# Communication.net
KiCad netlist of a schematic drawn in Altium Designer
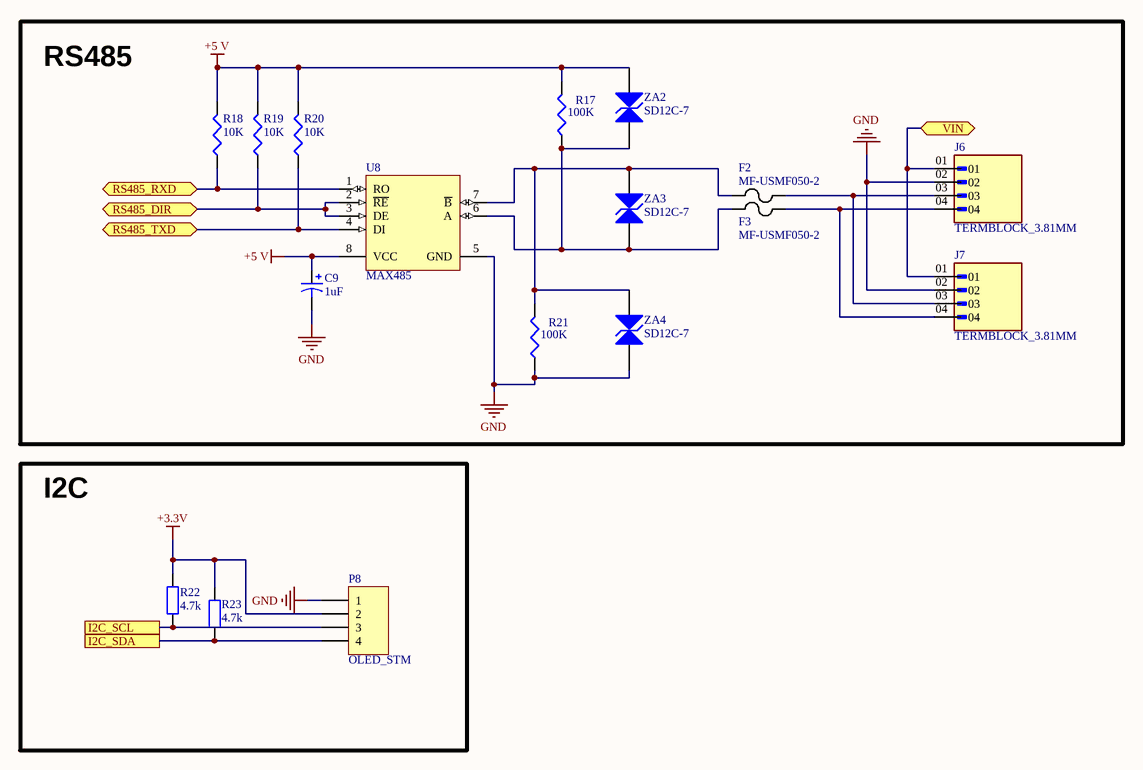
[diagram p0: Communication.SchDoc]

(export (version "E")
  (design (tool "Eeschema 10.0.6"))
  (components
    (comp (ref "C9")
      (value "1uF")
      (footprint "CAPC3225N")
      (description "Polarized Capacitor (Surface Mount)")
      (fields (field (name "PUBLISHER") "Altium Limited"))
      (libsource (lib "Miscellaneous Devices") (part "Cap Pol3"))
    )
    (comp (ref "F2")
      (value "MF-USMF050-2")
      (footprint "MF-USMF050-2")
      (description "PTC RESET FUSE 6V 3A 1812")
      (libsource (lib "Adox_Lib") (part "PTS18126V300"))
    )
    (comp (ref "F3")
      (value "MF-USMF050-2")
      (footprint "MF-USMF050-2")
      (description "PTC RESET FUSE 6V 3A 1812")
      (libsource (lib "Adox_Lib") (part "PTS18126V300"))
    )
    (comp (ref "J6")
      (value "TERMBLOCK_3.81MM")
      (footprint "TERMBLOCK_3.81MM_90DEG_4POS")
      (description "TERMBLOCK_3.81MM_90DEG_4POS (DigiKey: 1803293)")
      (libsource (lib "MH_Lib") (part "TERMBLOCK_3.81MM_90DEG_4POS"))
    )
    (comp (ref "J7")
      (value "TERMBLOCK_3.81MM")
      (footprint "TERMBLOCK_3.81MM_90DEG_4POS")
      (description "TERMBLOCK_3.81MM_90DEG_4POS (DigiKey: 1803293)")
      (libsource (lib "MH_Lib") (part "TERMBLOCK_3.81MM_90DEG_4POS"))
    )
    (comp (ref "P8")
      (value "OLED_STM")
      (footprint "CONNHDR_1X4_2.54MM")
      (description "Header, 4-Pin")
      (fields (field (name "PUBLISHER") "Altium Limited"))
      (libsource (lib "Miscellaneous Connectors") (part "MHDR1X4"))
    )
    (comp (ref "R17")
      (value "100K")
      (footprint "RESC2012N")
      (description "Resistor")
      (fields (field (name "PUBLISHER") "Altium Limited"))
      (libsource (lib "Miscellaneous Devices") (part "Res3"))
    )
    (comp (ref "R18")
      (value "10K")
      (footprint "RESC2012N")
      (description "Resistor")
      (fields (field (name "PUBLISHER") "Altium Limited"))
      (libsource (lib "Miscellaneous Devices") (part "Res3"))
    )
    (comp (ref "R19")
      (value "10K")
      (footprint "RESC2012N")
      (description "Resistor")
      (fields (field (name "PUBLISHER") "Altium Limited"))
      (libsource (lib "Miscellaneous Devices") (part "Res3"))
    )
    (comp (ref "R20")
      (value "10K")
      (footprint "RESC2012N")
      (description "Resistor")
      (fields (field (name "PUBLISHER") "Altium Limited"))
      (libsource (lib "Miscellaneous Devices") (part "Res3"))
    )
    (comp (ref "R21")
      (value "100K")
      (footprint "RESC2012N")
      (description "Resistor")
      (fields (field (name "PUBLISHER") "Altium Limited"))
      (libsource (lib "Miscellaneous Devices") (part "Res3"))
    )
    (comp (ref "R22")
      (value "4.7k")
      (footprint "RESC2012N")
      (description "Resistor")
      (fields (field (name "PUBLISHER") "Altium Limited"))
      (libsource (lib "Miscellaneous Devices") (part "Res2"))
    )
    (comp (ref "R23")
      (value "4.7k")
      (footprint "RESC2012N")
      (description "Resistor")
      (fields (field (name "PUBLISHER") "Altium Limited"))
      (libsource (lib "Miscellaneous Devices") (part "Res2"))
    )
    (comp (ref "U8")
      (value "MAX485")
      (footprint "MAX485")
      (description "Low-Power RS-485/RS-422 Multipoint Transceiver, 8-pin Narrow SOIC")
      (libsource (lib "MH_Lib") (part "MAX485"))
    )
    (comp (ref "ZA2")
      (value "SD12C-7")
      (footprint "SOD-323")
      (description "Transient voltage suppressor diode")
      (libsource (lib "Adox_Lib") (part "TVS Diode"))
    )
    (comp (ref "ZA3")
      (value "SD12C-7")
      (footprint "SOD-323")
      (description "Transient voltage suppressor diode")
      (libsource (lib "Adox_Lib") (part "TVS Diode"))
    )
    (comp (ref "ZA4")
      (value "SD12C-7")
      (footprint "SOD-323")
      (description "Transient voltage suppressor diode")
      (libsource (lib "Adox_Lib") (part "TVS Diode"))
    )
  )
  (nets
    (net (code "1") (name "+3.3V") (class "Default")
      (node (ref "P8") (pin "2") (pinfunction "2_2") (pintype "passive"))
      (node (ref "R22") (pin "2") (pinfunction "2_2") (pintype "passive"))
      (node (ref "R23") (pin "2") (pinfunction "2_2") (pintype "passive"))
    )
    (net (code "2") (name "+5 V") (class "Default")
      (node (ref "C9") (pin "1") (pinfunction "1_1") (pintype "passive"))
      (node (ref "R17") (pin "2") (pinfunction "2_2") (pintype "passive"))
      (node (ref "R18") (pin "2") (pinfunction "2_2") (pintype "passive"))
      (node (ref "R19") (pin "2") (pinfunction "2_2") (pintype "passive"))
      (node (ref "R20") (pin "2") (pinfunction "2_2") (pintype "passive"))
      (node (ref "U8") (pin "8") (pinfunction "VCC_8") (pintype "power_in"))
      (node (ref "ZA2") (pin "1") (pinfunction "1_1") (pintype "passive"))
    )
    (net (code "3") (name "/I2C_SCL") (class "Default")
      (node (ref "P8") (pin "3") (pinfunction "3_3") (pintype "passive"))
      (node (ref "R22") (pin "1") (pinfunction "1_1") (pintype "passive"))
    )
    (net (code "4") (name "/I2C_SDA") (class "Default")
      (node (ref "P8") (pin "4") (pinfunction "4_4") (pintype "passive"))
      (node (ref "R23") (pin "1") (pinfunction "1_1") (pintype "passive"))
    )
    (net (code "5") (name "/RS485_DIR") (class "Default")
      (node (ref "R19") (pin "1") (pinfunction "1_1") (pintype "passive"))
      (node (ref "U8") (pin "2") (pinfunction "~{RE}_2") (pintype "input"))
      (node (ref "U8") (pin "3") (pinfunction "DE_3") (pintype "input"))
    )
    (net (code "6") (name "/RS485_RXD") (class "Default")
      (node (ref "R18") (pin "1") (pinfunction "1_1") (pintype "passive"))
      (node (ref "U8") (pin "1") (pinfunction "RO_1") (pintype "bidirectional"))
    )
    (net (code "7") (name "/RS485_TXD") (class "Default")
      (node (ref "R20") (pin "1") (pinfunction "1_1") (pintype "passive"))
      (node (ref "U8") (pin "4") (pinfunction "DI_4") (pintype "input"))
    )
    (net (code "8") (name "/VIN") (class "Default")
      (node (ref "J6") (pin "01") (pinfunction "01_01") (pintype "passive"))
      (node (ref "J7") (pin "01") (pinfunction "01_01") (pintype "passive"))
    )
    (net (code "9") (name "GND") (class "Default")
      (node (ref "C9") (pin "2") (pinfunction "2_2") (pintype "passive"))
      (node (ref "J6") (pin "02") (pinfunction "02_02") (pintype "passive"))
      (node (ref "J7") (pin "02") (pinfunction "02_02") (pintype "passive"))
      (node (ref "P8") (pin "1") (pinfunction "1_1") (pintype "passive"))
      (node (ref "R21") (pin "1") (pinfunction "1_1") (pintype "passive"))
      (node (ref "U8") (pin "5") (pinfunction "GND_5") (pintype "power_in"))
      (node (ref "ZA4") (pin "2") (pinfunction "2_2") (pintype "passive"))
    )
    (net (code "10") (name "Net-(F2-Pad2)") (class "Default")
      (node (ref "F2") (pin "2") (pinfunction "2_2") (pintype "passive"))
      (node (ref "J6") (pin "03") (pinfunction "03_03") (pintype "passive"))
      (node (ref "J7") (pin "03") (pinfunction "03_03") (pintype "passive"))
    )
    (net (code "11") (name "Net-(F3-Pad2)") (class "Default")
      (node (ref "F3") (pin "2") (pinfunction "2_2") (pintype "passive"))
      (node (ref "J6") (pin "04") (pinfunction "04_04") (pintype "passive"))
      (node (ref "J7") (pin "04") (pinfunction "04_04") (pintype "passive"))
    )
    (net (code "12") (name "Net-(U8-A)") (class "Default")
      (node (ref "F3") (pin "1") (pinfunction "1_1") (pintype "passive"))
      (node (ref "R17") (pin "1") (pinfunction "1_1") (pintype "passive"))
      (node (ref "U8") (pin "6") (pinfunction "A_6") (pintype "bidirectional"))
      (node (ref "ZA2") (pin "2") (pinfunction "2_2") (pintype "passive"))
      (node (ref "ZA3") (pin "2") (pinfunction "2_2") (pintype "passive"))
    )
    (net (code "13") (name "Net-(U8-~{B})") (class "Default")
      (node (ref "F2") (pin "1") (pinfunction "1_1") (pintype "passive"))
      (node (ref "R21") (pin "2") (pinfunction "2_2") (pintype "passive"))
      (node (ref "U8") (pin "7") (pinfunction "~{B}_7") (pintype "bidirectional"))
      (node (ref "ZA3") (pin "1") (pinfunction "1_1") (pintype "passive"))
      (node (ref "ZA4") (pin "1") (pinfunction "1_1") (pintype "passive"))
    )
  )
)
